# BMS028B_FETs.net
KiCad netlist of a schematic drawn in Altium Designer
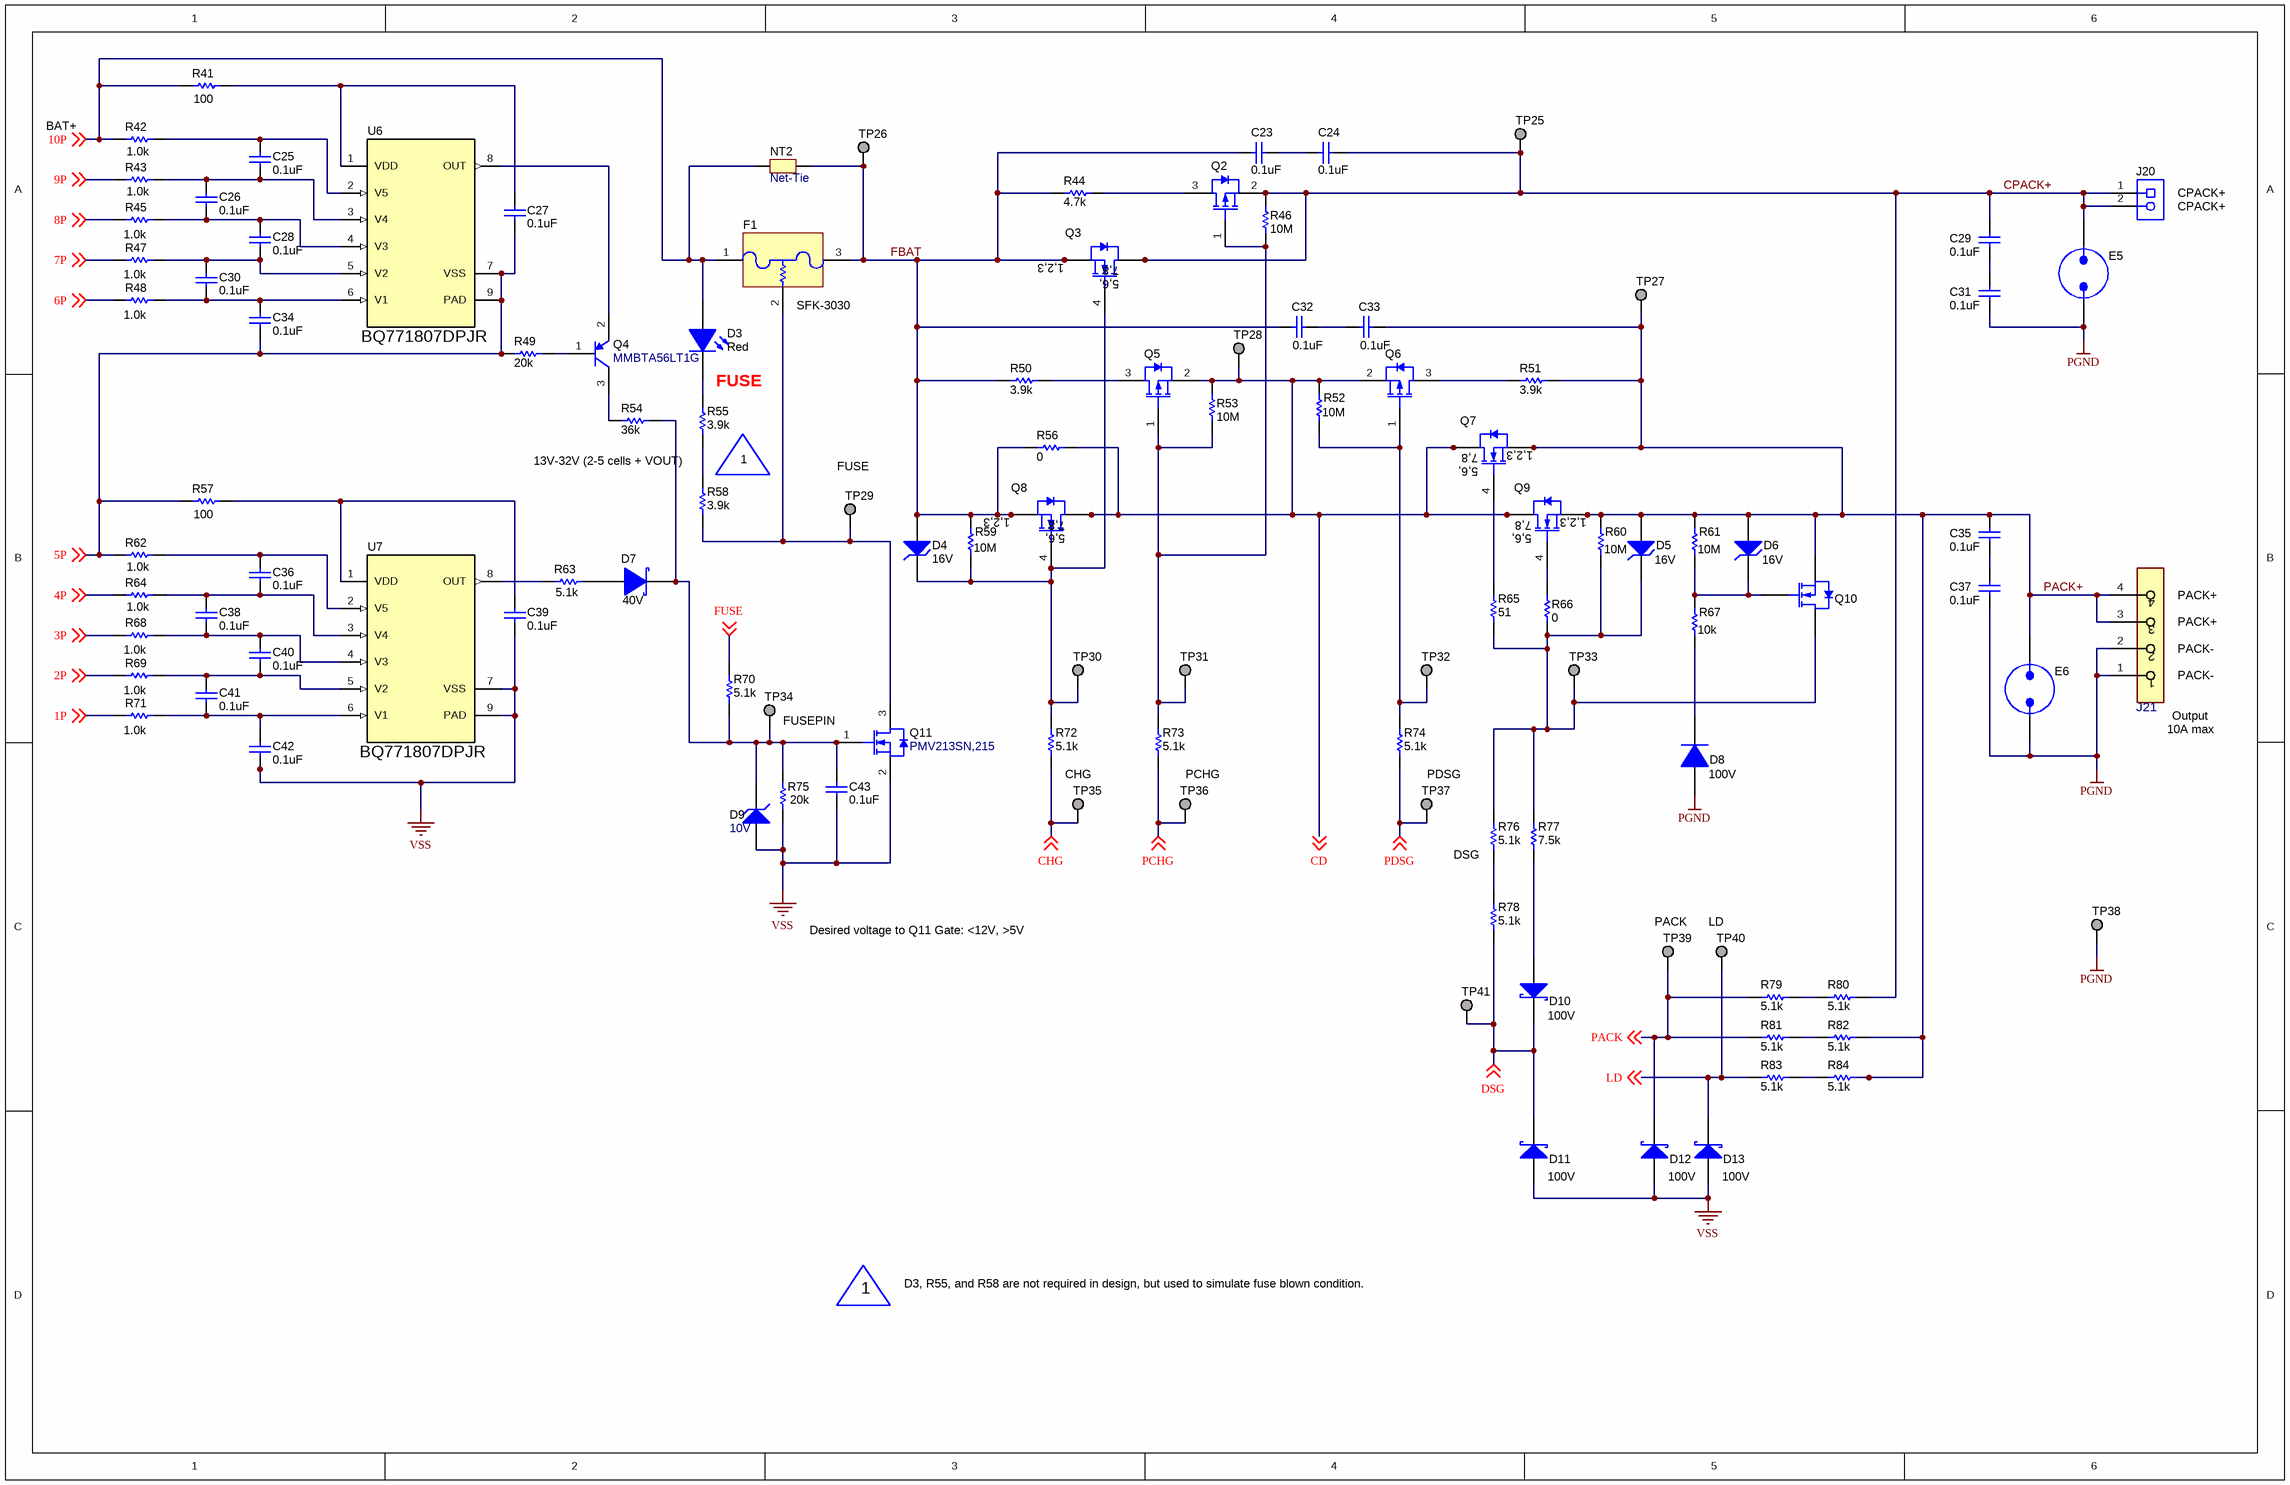
[diagram p0: BMS028B_FETs.SchDoc]

(export (version "E")
  (design (tool "Eeschema 10.0.6"))
  (components
    (comp (ref "C23")
      (value "GCJ188R72A104KA01D")
      (footprint "0603")
      (description "CAP, CERM, 0.1 uF, 100 V,+/- 10%, X7R, AEC-Q200 Grade 1, 0603")
      (fields
        (field (name "MANUFACTURER") "MuRata")
        (field (name "CAP_F") "0.1uF")
        (field (name "PUBLISHER") "Texas Instruments")
      )
      (libsource (lib "Altium Vault - TI") (part "Capacitor"))
    )
    (comp (ref "C24")
      (value "GCJ188R72A104KA01D")
      (footprint "0603")
      (description "CAP, CERM, 0.1 uF, 100 V,+/- 10%, X7R, AEC-Q200 Grade 1, 0603")
      (fields
        (field (name "MANUFACTURER") "MuRata")
        (field (name "CAP_F") "0.1uF")
        (field (name "PUBLISHER") "Texas Instruments")
      )
      (libsource (lib "Altium Vault - TI") (part "Capacitor"))
    )
    (comp (ref "C25")
      (value "885012206095")
      (footprint "0603")
      (description "CAP, CERM, 0.1 uF, 50 V, +/- 10%, X7R, 0603")
      (fields
        (field (name "VALUEDISPLAYED") "0.1uF")
        (field (name "MANUFACTURER") "Wurth Elektronik")
        (field (name "PUBLISHER") "Texas Instruments")
      )
      (libsource (lib "Altium Vault - TI") (part "Capacitor"))
    )
    (comp (ref "C26")
      (value "885012206095")
      (footprint "0603")
      (description "CAP, CERM, 0.1 uF, 50 V, +/- 10%, X7R, 0603")
      (fields
        (field (name "VALUEDISPLAYED") "0.1uF")
        (field (name "MANUFACTURER") "Wurth Elektronik")
        (field (name "PUBLISHER") "Texas Instruments")
      )
      (libsource (lib "Altium Vault - TI") (part "Capacitor"))
    )
    (comp (ref "C27")
      (value "885012206095")
      (footprint "0603")
      (description "CAP, CERM, 0.1 uF, 50 V, +/- 10%, X7R, 0603")
      (fields
        (field (name "VALUEDISPLAYED") "0.1uF")
        (field (name "MANUFACTURER") "Wurth Elektronik")
        (field (name "PUBLISHER") "Texas Instruments")
      )
      (libsource (lib "Altium Vault - TI") (part "Capacitor"))
    )
    (comp (ref "C28")
      (value "885012206095")
      (footprint "0603")
      (description "CAP, CERM, 0.1 uF, 50 V, +/- 10%, X7R, 0603")
      (fields
        (field (name "VALUEDISPLAYED") "0.1uF")
        (field (name "MANUFACTURER") "Wurth Elektronik")
        (field (name "PUBLISHER") "Texas Instruments")
      )
      (libsource (lib "Altium Vault - TI") (part "Capacitor"))
    )
    (comp (ref "C29")
      (value "GCJ188R72A104KA01D")
      (footprint "0603")
      (description "CAP, CERM, 0.1 uF, 100 V,+/- 10%, X7R, AEC-Q200 Grade 1, 0603")
      (fields
        (field (name "MANUFACTURER") "MuRata")
        (field (name "CAP_F") "0.1uF")
        (field (name "PUBLISHER") "Texas Instruments")
      )
      (libsource (lib "Altium Vault - TI") (part "Capacitor"))
    )
    (comp (ref "C30")
      (value "885012206095")
      (footprint "0603")
      (description "CAP, CERM, 0.1 uF, 50 V, +/- 10%, X7R, 0603")
      (fields
        (field (name "VALUEDISPLAYED") "0.1uF")
        (field (name "MANUFACTURER") "Wurth Elektronik")
        (field (name "PUBLISHER") "Texas Instruments")
      )
      (libsource (lib "Altium Vault - TI") (part "Capacitor"))
    )
    (comp (ref "C31")
      (value "GCJ188R72A104KA01D")
      (footprint "0603")
      (description "CAP, CERM, 0.1 uF, 100 V,+/- 10%, X7R, AEC-Q200 Grade 1, 0603")
      (fields
        (field (name "MANUFACTURER") "MuRata")
        (field (name "CAP_F") "0.1uF")
        (field (name "PUBLISHER") "Texas Instruments")
      )
      (libsource (lib "Altium Vault - TI") (part "Capacitor"))
    )
    (comp (ref "C32")
      (value "GCJ188R72A104KA01D")
      (footprint "0603")
      (description "CAP, CERM, 0.1 uF, 100 V,+/- 10%, X7R, AEC-Q200 Grade 1, 0603")
      (fields
        (field (name "MANUFACTURER") "MuRata")
        (field (name "VALUEDISPLAYED") "0.1uF")
        (field (name "PUBLISHER") "Texas Instruments")
      )
      (libsource (lib "Altium Vault - TI") (part "Capacitor"))
    )
    (comp (ref "C33")
      (value "GCJ188R72A104KA01D")
      (footprint "0603")
      (description "CAP, CERM, 0.1 uF, 100 V,+/- 10%, X7R, AEC-Q200 Grade 1, 0603")
      (fields
        (field (name "MANUFACTURER") "MuRata")
        (field (name "VALUEDISPLAYED") "0.1uF")
        (field (name "PUBLISHER") "Texas Instruments")
      )
      (libsource (lib "Altium Vault - TI") (part "Capacitor"))
    )
    (comp (ref "C34")
      (value "885012206095")
      (footprint "0603")
      (description "CAP, CERM, 0.1 uF, 50 V, +/- 10%, X7R, 0603")
      (fields
        (field (name "VALUEDISPLAYED") "0.1uF")
        (field (name "MANUFACTURER") "Wurth Elektronik")
        (field (name "PUBLISHER") "Texas Instruments")
      )
      (libsource (lib "Altium Vault - TI") (part "Capacitor"))
    )
    (comp (ref "C35")
      (value "GCJ188R72A104KA01D")
      (footprint "0603")
      (description "CAP, CERM, 0.1 uF, 100 V,+/- 10%, X7R, AEC-Q200 Grade 1, 0603")
      (fields
        (field (name "MANUFACTURER") "MuRata")
        (field (name "CAP_F") "0.1uF")
        (field (name "PUBLISHER") "Texas Instruments")
      )
      (libsource (lib "Altium Vault - TI") (part "Capacitor"))
    )
    (comp (ref "C36")
      (value "885012206095")
      (footprint "0603")
      (description "CAP, CERM, 0.1 uF, 50 V, +/- 10%, X7R, 0603")
      (fields
        (field (name "VALUEDISPLAYED") "0.1uF")
        (field (name "MANUFACTURER") "Wurth Elektronik")
        (field (name "PUBLISHER") "Texas Instruments")
      )
      (libsource (lib "Altium Vault - TI") (part "Capacitor"))
    )
    (comp (ref "C37")
      (value "GCJ188R72A104KA01D")
      (footprint "0603")
      (description "CAP, CERM, 0.1 uF, 100 V,+/- 10%, X7R, AEC-Q200 Grade 1, 0603")
      (fields
        (field (name "MANUFACTURER") "MuRata")
        (field (name "CAP_F") "0.1uF")
        (field (name "PUBLISHER") "Texas Instruments")
      )
      (libsource (lib "Altium Vault - TI") (part "Capacitor"))
    )
    (comp (ref "C38")
      (value "885012206095")
      (footprint "0603")
      (description "CAP, CERM, 0.1 uF, 50 V, +/- 10%, X7R, 0603")
      (fields
        (field (name "VALUEDISPLAYED") "0.1uF")
        (field (name "MANUFACTURER") "Wurth Elektronik")
        (field (name "PUBLISHER") "Texas Instruments")
      )
      (libsource (lib "Altium Vault - TI") (part "Capacitor"))
    )
    (comp (ref "C39")
      (value "885012206095")
      (footprint "0603")
      (description "CAP, CERM, 0.1 uF, 50 V, +/- 10%, X7R, 0603")
      (fields
        (field (name "VALUEDISPLAYED") "0.1uF")
        (field (name "MANUFACTURER") "Wurth Elektronik")
        (field (name "PUBLISHER") "Texas Instruments")
      )
      (libsource (lib "Altium Vault - TI") (part "Capacitor"))
    )
    (comp (ref "C40")
      (value "885012206095")
      (footprint "0603")
      (description "CAP, CERM, 0.1 uF, 50 V, +/- 10%, X7R, 0603")
      (fields
        (field (name "VALUEDISPLAYED") "0.1uF")
        (field (name "MANUFACTURER") "Wurth Elektronik")
        (field (name "PUBLISHER") "Texas Instruments")
      )
      (libsource (lib "Altium Vault - TI") (part "Capacitor"))
    )
    (comp (ref "C41")
      (value "885012206095")
      (footprint "0603")
      (description "CAP, CERM, 0.1 uF, 50 V, +/- 10%, X7R, 0603")
      (fields
        (field (name "VALUEDISPLAYED") "0.1uF")
        (field (name "MANUFACTURER") "Wurth Elektronik")
        (field (name "PUBLISHER") "Texas Instruments")
      )
      (libsource (lib "Altium Vault - TI") (part "Capacitor"))
    )
    (comp (ref "C42")
      (value "885012206095")
      (footprint "0603")
      (description "CAP, CERM, 0.1 uF, 50 V, +/- 10%, X7R, 0603")
      (fields
        (field (name "VALUEDISPLAYED") "0.1uF")
        (field (name "MANUFACTURER") "Wurth Elektronik")
        (field (name "PUBLISHER") "Texas Instruments")
      )
      (libsource (lib "Altium Vault - TI") (part "Capacitor"))
    )
    (comp (ref "C43")
      (value "885012206095")
      (footprint "0603")
      (description "CAP, CERM, 0.1 uF, 50 V, +/- 10%, X7R, 0603")
      (fields
        (field (name "VALUEDISPLAYED") "0.1uF")
        (field (name "MANUFACTURER") "Wurth Elektronik")
        (field (name "PUBLISHER") "Texas Instruments")
      )
      (libsource (lib "Altium Vault - TI") (part "Capacitor"))
    )
    (comp (ref "D3")
      (value "Red")
      (footprint "WL-SMCW_RED")
      (description "LED, Red, SMD")
      (fields (field (name "MANUFACTURER") "Wurth Elektronik") (field (name "PARTNUMBER") "150060RS75000"))
      (libsource (lib "Altium Vault - TI") (part "CMP-0002947-3"))
    )
    (comp (ref "D4")
      (value "16V")
      (footprint "SOD-123")
      (description "Diode, Zener, 16 V, 500 mW, SOD-123")
      (fields (field (name "MANUFACTURER") "Diodes Inc.") (field (name "PARTNUMBER") "MMSZ5246B-7-F"))
      (libsource (lib "Altium Vault - TI") (part "Zener"))
    )
    (comp (ref "D5")
      (value "16V")
      (footprint "SOD-123")
      (description "Diode, Zener, 16 V, 500 mW, SOD-123")
      (fields (field (name "PARTNUMBER") "MMSZ5246B-7-F") (field (name "MANUFACTURER") "Diodes Inc."))
      (libsource (lib "Altium Vault - TI") (part "CMP-0005754-4"))
    )
    (comp (ref "D6")
      (value "16V")
      (footprint "SOD-123")
      (description "Diode, Zener, 16 V, 500 mW, SOD-123")
      (fields (field (name "PARTNUMBER") "MMSZ5246B-7-F") (field (name "MANUFACTURER") "Diodes Inc."))
      (libsource (lib "Altium Vault - TI") (part "CMP-0005754-4"))
    )
    (comp (ref "D7")
      (value "40V")
      (footprint "SOT-323")
      (description "Diode, Schottky, 40 V, 0.2 A, SOT-323")
      (fields (field (name "PARTNUMBER") "BAS40W-7-F") (field (name "MANUFACTURER") "Diodes Inc."))
      (libsource (lib "Altium Vault - TI") (part "CMP-0028438-2"))
    )
    (comp (ref "D8")
      (value "100V")
      (footprint "SOD-123")
      (description "Diode, Ultrafast, 100 V, 0.15 A, SOD-123")
      (fields (field (name "PARTNUMBER") "1N4148W-7-F") (field (name "MANUFACTURER") "Diodes Inc."))
      (libsource (lib "Altium Vault - TI") (part "CMP-0029001-2"))
    )
    (comp (ref "D9")
      (value "10V")
      (footprint "SOD-123")
      (description "Diode, Zener, 10 V, 500 mW, SOD-123")
      (fields (field (name "MANUFACTURER") "ON Semiconductor") (field (name "PARTNUMBER") "MMSZ4697T1G"))
      (libsource (lib "Altium Vault - TI") (part "Zener"))
    )
    (comp (ref "D10")
      (value "BAT46W-7-F")
      (footprint "SOD-123")
      (description "Diode, Schottky, 100 V, 0.15 A, SOD-123")
      (fields (field (name "MANUFACTURER") "Diodes Inc.") (field (name "VR_V") "100V"))
      (libsource (lib "Altium Vault - TI") (part "DIODE_SCHOTTKY"))
    )
    (comp (ref "D11")
      (value "BAT46W-7-F")
      (footprint "SOD-123")
      (description "Diode, Schottky, 100 V, 0.15 A, SOD-123")
      (fields (field (name "MANUFACTURER") "Diodes Inc.") (field (name "VR_V") "100V"))
      (libsource (lib "Altium Vault - TI") (part "DIODE_SCHOTTKY"))
    )
    (comp (ref "D12")
      (value "BAT46W-7-F")
      (footprint "SOD-123")
      (description "Diode, Schottky, 100 V, 0.15 A, SOD-123")
      (fields (field (name "MANUFACTURER") "Diodes Inc.") (field (name "VR_V") "100V"))
      (libsource (lib "Altium Vault - TI") (part "DIODE_SCHOTTKY"))
    )
    (comp (ref "D13")
      (value "BAT46W-7-F")
      (footprint "SOD-123")
      (description "Diode, Schottky, 100 V, 0.15 A, SOD-123")
      (fields (field (name "MANUFACTURER") "Diodes Inc.") (field (name "VR_V") "100V"))
      (libsource (lib "Altium Vault - TI") (part "DIODE_SCHOTTKY"))
    )
    (comp (ref "E5")
      (value "Spark Gap")
      (footprint "SPARK_GAP2")
      (libsource (lib "Altium Vault - TI") (part "CMP-0079939-1"))
    )
    (comp (ref "E6")
      (value "Spark Gap")
      (footprint "SPARK_GAP2")
      (libsource (lib "Altium Vault - TI") (part "CMP-0079939-1"))
    )
    (comp (ref "F1")
      (value "SFK-3030")
      (footprint "FUSE_SFK-xx30x")
      (description "Fuse, 30 A, 62 VDC, SMD")
      (fields (field (name "MANUFACTURER") "Dexerials Corporation"))
      (libsource (lib "Altium Vault - TI") (part "FUSE_SFK-XX30X"))
    )
    (comp (ref "J20")
      (value "ED555/2DS")
      (footprint "TERM_BLK_ED555-2DS")
      (description "Terminal Block, 3.5mm Pitch, 2x1, TH")
      (fields
        (field (name "MANUFACTURER") "On-Shore Technology")
        (field (name "PUBLISHER") "Texas Instruments")
      )
      (libsource (lib "Altium Vault - TI") (part "CMP-0074913-1"))
    )
    (comp (ref "J21")
      (value "OSTTE040161")
      (footprint "FP-OSTTE040161_HDR4-MFG")
      (description "TERM BLOCK 3.5MM VERT 4POS PCB")
      (fields (field (name "MANUFACTURER") "On Shore Technology"))
      (libsource (lib "Altium Vault - TI") (part "SYM-OSTTE040161"))
    )
    (comp (ref "NT2")
      (value "Net-Tie")
      (footprint "Net-Tie_50milWide_30milLong")
      (description "Single point connection between nets.")
      (libsource (lib "Altium Vault - TI") (part "Net-Tie"))
    )
    (comp (ref "Q2")
      (value "ZXMP10A13FTA")
      (footprint "SOT-23")
      (description "MOSFET, P-CH, -100 V, -0.6 A, SOT-23")
      (fields (field (name "MANUFACTURER") "Diodes Inc."))
      (libsource (lib "Altium Vault - TI") (part "MOSFET_P_D3G1S2"))
    )
    (comp (ref "Q3")
      (value "CSD19534Q5A")
      (footprint "DQJ0008A")
      (description "MOSFET, N-CH, 100 V, 10 A, DQJ0008A (VSONP-8)")
      (fields
        (field (name "MANUFACTURER") "Texas Instruments")
        (field (name "PUBLISHER") "Texas Instruments")
      )
      (libsource (lib "Altium Vault - TI") (part "MOSFET_N_D56789G4S123"))
    )
    (comp (ref "Q4")
      (value "MMBTA56LT1G")
      (footprint "SOT-23")
      (description "Transistor, PNP, 80 V, 0.5 A, SOT-23")
      (fields (field (name "MANUFACTURER") "ON Semiconductor") (field (name "PUBLISHER") "Texas Instruments"))
      (libsource (lib "Altium Vault - TI") (part "BJT_PNP_C3B1E2"))
    )
    (comp (ref "Q5")
      (value "ZXMP10A13FTA")
      (footprint "SOT-23")
      (description "MOSFET, P-CH, -100 V, -0.6 A, SOT-23")
      (fields (field (name "MANUFACTURER") "Diodes Inc."))
      (libsource (lib "Altium Vault - TI") (part "MOSFET_P_D3G1S2"))
    )
    (comp (ref "Q6")
      (value "ZXMP10A13FTA")
      (footprint "SOT-23")
      (description "MOSFET, P-CH, -100 V, -0.6 A, SOT-23")
      (fields (field (name "MANUFACTURER") "Diodes Inc."))
      (libsource (lib "Altium Vault - TI") (part "MOSFET_P_D3G1S2"))
    )
    (comp (ref "Q7")
      (value "CSD19532Q5B")
      (footprint "DNK0008A")
      (description "MOSFET, N-CH, 100 V, 17 A, DNK0008A (VSON-CLIP-8)")
      (fields (field (name "MANUFACTURER") "Texas Instruments"))
      (libsource (lib "Altium Vault - TI") (part "MOSFET_N_D56789G4S123"))
    )
    (comp (ref "Q8")
      (value "CSD19532Q5B")
      (footprint "DNK0008A")
      (description "MOSFET, N-CH, 100 V, 17 A, DNK0008A (VSON-CLIP-8)")
      (fields (field (name "MANUFACTURER") "Texas Instruments"))
      (libsource (lib "Altium Vault - TI") (part "MOSFET_N_D56789G4S123"))
    )
    (comp (ref "Q9")
      (value "CSD19532Q5B")
      (footprint "DNK0008A")
      (description "MOSFET, N-CH, 100 V, 17 A, DNK0008A (VSON-CLIP-8)")
      (fields (field (name "MANUFACTURER") "Texas Instruments"))
      (libsource (lib "Altium Vault - TI") (part "MOSFET_N_D56789G4S123"))
    )
    (comp (ref "Q10")
      (value "MOSFET_N_D3G1S2")
      (footprint "SOT-323")
      (description "MOSFET, N-CH, 60 V, 0.31 A, SOT-323")
      (fields
        (field (name "PARTNUMBER") "2N7002KW")
        (field (name "MANUFACTURER") "Fairchild Semiconductor")
        (field (name "PUBLISHER") "Texas Instruments")
      )
      (libsource (lib "Altium Vault - TI") (part "CMP-0000774-1"))
    )
    (comp (ref "Q11")
      (value "PMV213SN,215")
      (footprint "SOT-23")
      (description "MOSFET, N-CH, 100 V, 1.9 A, SOT-23")
      (fields (field (name "MANUFACTURER") "Nexperia"))
      (libsource (lib "Altium Vault - TI") (part "MOSFET_N_D3G1S2"))
    )
    (comp (ref "R41")
      (value "Resistor")
      (footprint "0603")
      (description "RES, 100, 5%, 0.1 W, AEC-Q200 Grade 0, 0603")
      (fields
        (field (name "PARTNUMBER") "CRCW0603100RJNEA")
        (field (name "MANUFACTURER") "Vishay-Dale")
        (field (name "VALUEDISPLAYED") "100")
        (field (name "PUBLISHER") "Texas Instruments")
      )
      (libsource (lib "Altium Vault - TI") (part "Resistor"))
    )
    (comp (ref "R42")
      (value "Resistor")
      (footprint "0603")
      (description "RES, 1.0 k, 5%, 0.1 W, AEC-Q200 Grade 0, 0603")
      (fields
        (field (name "PARTNUMBER") "CRCW06031K00JNEA")
        (field (name "MANUFACTURER") "Vishay-Dale")
        (field (name "VALUEDISPLAYED") "1.0k")
        (field (name "PUBLISHER") "Texas Instruments")
      )
      (libsource (lib "Altium Vault - TI") (part "Resistor"))
    )
    (comp (ref "R43")
      (value "Resistor")
      (footprint "0603")
      (description "RES, 1.0 k, 5%, 0.1 W, AEC-Q200 Grade 0, 0603")
      (fields
        (field (name "PARTNUMBER") "CRCW06031K00JNEA")
        (field (name "MANUFACTURER") "Vishay-Dale")
        (field (name "VALUEDISPLAYED") "1.0k")
        (field (name "PUBLISHER") "Texas Instruments")
      )
      (libsource (lib "Altium Vault - TI") (part "Resistor"))
    )
    (comp (ref "R44")
      (value "CRCW25124K70JNEG")
      (footprint "2512")
      (description "RES, 4.7 k, 5%, 1 W, AEC-Q200 Grade 0, 2512")
      (fields (field (name "MANUFACTURER") "Vishay-Dale") (field (name "VALUEDISPLAYED") "4.7k"))
      (libsource (lib "Altium Vault - TI") (part "Resistor"))
    )
    (comp (ref "R45")
      (value "Resistor")
      (footprint "0603")
      (description "RES, 1.0 k, 5%, 0.1 W, AEC-Q200 Grade 0, 0603")
      (fields
        (field (name "PARTNUMBER") "CRCW06031K00JNEA")
        (field (name "MANUFACTURER") "Vishay-Dale")
        (field (name "VALUEDISPLAYED") "1.0k")
        (field (name "PUBLISHER") "Texas Instruments")
      )
      (libsource (lib "Altium Vault - TI") (part "Resistor"))
    )
    (comp (ref "R46")
      (value "Resistor")
      (footprint "0603")
      (description "RES, 10 M, 5%, 0.1 W, AEC-Q200 Grade 0, 0603")
      (fields
        (field (name "PARTNUMBER") "CRCW060310M0JNEA")
        (field (name "MANUFACTURER") "Vishay-Dale")
        (field (name "VALUEDISPLAYED") "10M")
        (field (name "PUBLISHER") "Texas Instruments")
      )
      (libsource (lib "Altium Vault - TI") (part "Resistor"))
    )
    (comp (ref "R47")
      (value "Resistor")
      (footprint "0603")
      (description "RES, 1.0 k, 5%, 0.1 W, AEC-Q200 Grade 0, 0603")
      (fields
        (field (name "PARTNUMBER") "CRCW06031K00JNEA")
        (field (name "MANUFACTURER") "Vishay-Dale")
        (field (name "VALUEDISPLAYED") "1.0k")
        (field (name "PUBLISHER") "Texas Instruments")
      )
      (libsource (lib "Altium Vault - TI") (part "Resistor"))
    )
    (comp (ref "R48")
      (value "Resistor")
      (footprint "0603")
      (description "RES, 1.0 k, 5%, 0.1 W, AEC-Q200 Grade 0, 0603")
      (fields
        (field (name "PARTNUMBER") "CRCW06031K00JNEA")
        (field (name "MANUFACTURER") "Vishay-Dale")
        (field (name "VALUEDISPLAYED") "1.0k")
        (field (name "PUBLISHER") "Texas Instruments")
      )
      (libsource (lib "Altium Vault - TI") (part "Resistor"))
    )
    (comp (ref "R49")
      (value "CRCW060320K0JNEA")
      (footprint "0603")
      (description "RES, 20 k, 5%, 0.1 W, AEC-Q200 Grade 0, 0603")
      (fields (field (name "MANUFACTURER") "Vishay-Dale") (field (name "VALUEDISPLAYED") "20k"))
      (libsource (lib "Altium Vault - TI") (part "Resistor"))
    )
    (comp (ref "R50")
      (value "CRCW25123K90JNEG")
      (footprint "2512")
      (description "RES, 3.9 k, 5%, 1 W, AEC-Q200 Grade 0, 2512")
      (fields (field (name "MANUFACTURER") "Vishay-Dale") (field (name "VALUEDISPLAYED") "3.9k"))
      (libsource (lib "Altium Vault - TI") (part "Resistor"))
    )
    (comp (ref "R51")
      (value "CRCW25123K90JNEG")
      (footprint "2512")
      (description "RES, 3.9 k, 5%, 1 W, AEC-Q200 Grade 0, 2512")
      (fields (field (name "MANUFACTURER") "Vishay-Dale") (field (name "VALUEDISPLAYED") "3.9k"))
      (libsource (lib "Altium Vault - TI") (part "Resistor"))
    )
    (comp (ref "R52")
      (value "Resistor")
      (footprint "0603")
      (description "RES, 10 M, 5%, 0.1 W, AEC-Q200 Grade 0, 0603")
      (fields
        (field (name "PARTNUMBER") "CRCW060310M0JNEA")
        (field (name "MANUFACTURER") "Vishay-Dale")
        (field (name "VALUEDISPLAYED") "10M")
        (field (name "PUBLISHER") "Texas Instruments")
      )
      (libsource (lib "Altium Vault - TI") (part "Resistor"))
    )
    (comp (ref "R53")
      (value "Resistor")
      (footprint "0603")
      (description "RES, 10 M, 5%, 0.1 W, AEC-Q200 Grade 0, 0603")
      (fields
        (field (name "PARTNUMBER") "CRCW060310M0JNEA")
        (field (name "MANUFACTURER") "Vishay-Dale")
        (field (name "VALUEDISPLAYED") "10M")
        (field (name "PUBLISHER") "Texas Instruments")
      )
      (libsource (lib "Altium Vault - TI") (part "Resistor"))
    )
    (comp (ref "R54")
      (value "CRCW060336K0JNEA")
      (footprint "0603")
      (description "RES, 36 k, 5%, 0.1 W, AEC-Q200 Grade 0, 0603")
      (fields (field (name "MANUFACTURER") "Vishay-Dale") (field (name "VALUEDISPLAYED") "36k"))
      (libsource (lib "Altium Vault - TI") (part "Resistor"))
    )
    (comp (ref "R55")
      (value "CRCW12063K90JNEA")
      (footprint "1206")
      (description "RES, 3.9 k, 5%, 0.25 W, AEC-Q200 Grade 0, 1206")
      (fields (field (name "MANUFACTURER") "Vishay-Dale") (field (name "VALUEDISPLAYED") "3.9k"))
      (libsource (lib "Altium Vault - TI") (part "Resistor"))
    )
    (comp (ref "R56")
      (value "Resistor")
      (footprint "2512_WIDE_VISHAY")
      (description "RES, 0, 5%, 2 W, 2512 WIDE")
      (fields
        (field (name "PARTNUMBER") "RCL12250000Z0EG")
        (field (name "VALUEDISPLAYED") "0")
        (field (name "MANUFACTURER") "Vishay Draloric")
        (field (name "PUBLISHER") "Texas Instruments")
      )
      (libsource (lib "Altium Vault - TI") (part "Resistor"))
    )
    (comp (ref "R57")
      (value "Resistor")
      (footprint "0603")
      (description "RES, 100, 5%, 0.1 W, AEC-Q200 Grade 0, 0603")
      (fields
        (field (name "PARTNUMBER") "CRCW0603100RJNEA")
        (field (name "MANUFACTURER") "Vishay-Dale")
        (field (name "VALUEDISPLAYED") "100")
        (field (name "PUBLISHER") "Texas Instruments")
      )
      (libsource (lib "Altium Vault - TI") (part "Resistor"))
    )
    (comp (ref "R58")
      (value "CRCW12063K90JNEA")
      (footprint "1206")
      (description "RES, 3.9 k, 5%, 0.25 W, AEC-Q200 Grade 0, 1206")
      (fields (field (name "MANUFACTURER") "Vishay-Dale") (field (name "VALUEDISPLAYED") "3.9k"))
      (libsource (lib "Altium Vault - TI") (part "Resistor"))
    )
    (comp (ref "R59")
      (value "Resistor")
      (footprint "0603")
      (description "RES, 10 M, 5%, 0.1 W, AEC-Q200 Grade 0, 0603")
      (fields
        (field (name "PARTNUMBER") "CRCW060310M0JNEA")
        (field (name "MANUFACTURER") "Vishay-Dale")
        (field (name "VALUEDISPLAYED") "10M")
        (field (name "PUBLISHER") "Texas Instruments")
      )
      (libsource (lib "Altium Vault - TI") (part "Resistor"))
    )
    (comp (ref "R60")
      (value "Resistor")
      (footprint "0603")
      (description "RES, 10 M, 5%, 0.1 W, AEC-Q200 Grade 0, 0603")
      (fields
        (field (name "PARTNUMBER") "CRCW060310M0JNEA")
        (field (name "MANUFACTURER") "Vishay-Dale")
        (field (name "VALUEDISPLAYED") "10M")
        (field (name "PUBLISHER") "Texas Instruments")
      )
      (libsource (lib "Altium Vault - TI") (part "Resistor"))
    )
    (comp (ref "R61")
      (value "Resistor")
      (footprint "0603")
      (description "RES, 10 M, 5%, 0.1 W, AEC-Q200 Grade 0, 0603")
      (fields
        (field (name "PARTNUMBER") "CRCW060310M0JNEA")
        (field (name "MANUFACTURER") "Vishay-Dale")
        (field (name "VALUEDISPLAYED") "10M")
        (field (name "PUBLISHER") "Texas Instruments")
      )
      (libsource (lib "Altium Vault - TI") (part "Resistor"))
    )
    (comp (ref "R62")
      (value "Resistor")
      (footprint "0603")
      (description "RES, 1.0 k, 5%, 0.1 W, AEC-Q200 Grade 0, 0603")
      (fields
        (field (name "PARTNUMBER") "CRCW06031K00JNEA")
        (field (name "MANUFACTURER") "Vishay-Dale")
        (field (name "VALUEDISPLAYED") "1.0k")
        (field (name "PUBLISHER") "Texas Instruments")
      )
      (libsource (lib "Altium Vault - TI") (part "Resistor"))
    )
    (comp (ref "R63")
      (value "Resistor")
      (footprint "0603")
      (description "RES, 5.1 k, 5%, 0.1 W, AEC-Q200 Grade 0, 0603")
      (fields
        (field (name "PARTNUMBER") "CRCW06035K10JNEA")
        (field (name "MANUFACTURER") "Vishay-Dale")
        (field (name "VALUEDISPLAYED") "5.1k")
        (field (name "PUBLISHER") "Texas Instruments")
      )
      (libsource (lib "Altium Vault - TI") (part "Resistor"))
    )
    (comp (ref "R64")
      (value "Resistor")
      (footprint "0603")
      (description "RES, 1.0 k, 5%, 0.1 W, AEC-Q200 Grade 0, 0603")
      (fields
        (field (name "PARTNUMBER") "CRCW06031K00JNEA")
        (field (name "MANUFACTURER") "Vishay-Dale")
        (field (name "VALUEDISPLAYED") "1.0k")
        (field (name "PUBLISHER") "Texas Instruments")
      )
      (libsource (lib "Altium Vault - TI") (part "Resistor"))
    )
    (comp (ref "R65")
      (value "CRCW060351R0JNEA")
      (footprint "0603")
      (description "RES, 51, 5%, 0.1 W, AEC-Q200 Grade 0, 0603")
      (fields (field (name "MANUFACTURER") "Vishay-Dale") (field (name "VALUEDISPLAYED") "51"))
      (libsource (lib "Altium Vault - TI") (part "Resistor"))
    )
    (comp (ref "R66")
      (value "CRCW06030000Z0EA")
      (footprint "0603")
      (description "RES, 0, 5%, 0.1 W, AEC-Q200 Grade 0, 0603")
      (fields (field (name "MANUFACTURER") "Vishay-Dale") (field (name "VALUEDISPLAYED") "0"))
      (libsource (lib "Altium Vault - TI") (part "Resistor"))
    )
    (comp (ref "R67")
      (value "Resistor")
      (footprint "0603")
      (description "RES, 10 k, 5%, 0.1 W, AEC-Q200 Grade 0, 0603")
      (fields
        (field (name "PARTNUMBER") "CRCW060310K0JNEA")
        (field (name "MANUFACTURER") "Vishay-Dale")
        (field (name "VALUEDISPLAYED") "10k")
        (field (name "PUBLISHER") "Texas Instruments")
      )
      (libsource (lib "Altium Vault - TI") (part "Resistor"))
    )
    (comp (ref "R68")
      (value "Resistor")
      (footprint "0603")
      (description "RES, 1.0 k, 5%, 0.1 W, AEC-Q200 Grade 0, 0603")
      (fields
        (field (name "PARTNUMBER") "CRCW06031K00JNEA")
        (field (name "MANUFACTURER") "Vishay-Dale")
        (field (name "VALUEDISPLAYED") "1.0k")
        (field (name "PUBLISHER") "Texas Instruments")
      )
      (libsource (lib "Altium Vault - TI") (part "Resistor"))
    )
    (comp (ref "R69")
      (value "Resistor")
      (footprint "0603")
      (description "RES, 1.0 k, 5%, 0.1 W, AEC-Q200 Grade 0, 0603")
      (fields
        (field (name "PARTNUMBER") "CRCW06031K00JNEA")
        (field (name "MANUFACTURER") "Vishay-Dale")
        (field (name "VALUEDISPLAYED") "1.0k")
        (field (name "PUBLISHER") "Texas Instruments")
      )
      (libsource (lib "Altium Vault - TI") (part "Resistor"))
    )
    (comp (ref "R70")
      (value "Resistor")
      (footprint "0603")
      (description "RES, 5.1 k, 5%, 0.1 W, AEC-Q200 Grade 0, 0603")
      (fields
        (field (name "PARTNUMBER") "CRCW06035K10JNEA")
        (field (name "MANUFACTURER") "Vishay-Dale")
        (field (name "VALUEDISPLAYED") "5.1k")
        (field (name "PUBLISHER") "Texas Instruments")
      )
      (libsource (lib "Altium Vault - TI") (part "Resistor"))
    )
    (comp (ref "R71")
      (value "Resistor")
      (footprint "0603")
      (description "RES, 1.0 k, 5%, 0.1 W, AEC-Q200 Grade 0, 0603")
      (fields
        (field (name "PARTNUMBER") "CRCW06031K00JNEA")
        (field (name "MANUFACTURER") "Vishay-Dale")
        (field (name "VALUEDISPLAYED") "1.0k")
        (field (name "PUBLISHER") "Texas Instruments")
      )
      (libsource (lib "Altium Vault - TI") (part "Resistor"))
    )
    (comp (ref "R72")
      (value "CRCW06035K10JNEA")
      (footprint "0603")
      (description "RES, 5.1 k, 5%, 0.1 W, AEC-Q200 Grade 0, 0603")
      (fields (field (name "VALUEDISPLAYED") "5.1k") (field (name "MANUFACTURER") "Vishay-Dale"))
      (libsource (lib "Altium Vault - TI") (part "Resistor"))
    )
    (comp (ref "R73")
      (value "CRCW06035K10JNEA")
      (footprint "0603")
      (description "RES, 5.1 k, 5%, 0.1 W, AEC-Q200 Grade 0, 0603")
      (fields (field (name "VALUEDISPLAYED") "5.1k") (field (name "MANUFACTURER") "Vishay-Dale"))
      (libsource (lib "Altium Vault - TI") (part "Resistor"))
    )
    (comp (ref "R74")
      (value "CRCW06035K10JNEA")
      (footprint "0603")
      (description "RES, 5.1 k, 5%, 0.1 W, AEC-Q200 Grade 0, 0603")
      (fields (field (name "MANUFACTURER") "Vishay-Dale") (field (name "VALUEDISPLAYED") "5.1k"))
      (libsource (lib "Altium Vault - TI") (part "Resistor"))
    )
    (comp (ref "R75")
      (value "Resistor")
      (footprint "0603")
      (description "RES, 20 k, 5%, 0.1 W, AEC-Q200 Grade 0, 0603")
      (fields
        (field (name "PARTNUMBER") "CRCW060320K0JNEA")
        (field (name "MANUFACTURER") "Vishay-Dale")
        (field (name "VALUEDISPLAYED") "20k")
        (field (name "PUBLISHER") "Texas Instruments")
      )
      (libsource (lib "Altium Vault - TI") (part "Resistor"))
    )
    (comp (ref "R76")
      (value "CRCW12065K10JNEA")
      (footprint "1206")
      (description "RES, 5.1 k, 5%, 0.25 W, AEC-Q200 Grade 0, 1206")
      (fields (field (name "VALUEDISPLAYED") "5.1k") (field (name "MANUFACTURER") "Vishay-Dale"))
      (libsource (lib "Altium Vault - TI") (part "Resistor"))
    )
    (comp (ref "R77")
      (value "CRCW06037K50JNEA")
      (footprint "0603")
      (description "RES, 7.5 k, 5%, 0.1 W, AEC-Q200 Grade 0, 0603")
      (fields (field (name "MANUFACTURER") "Vishay-Dale") (field (name "VALUEDISPLAYED") "7.5k"))
      (libsource (lib "Altium Vault - TI") (part "Resistor"))
    )
    (comp (ref "R78")
      (value "CRCW12065K10JNEA")
      (footprint "1206")
      (description "RES, 5.1 k, 5%, 0.25 W, AEC-Q200 Grade 0, 1206")
      (fields (field (name "VALUEDISPLAYED") "5.1k") (field (name "MANUFACTURER") "Vishay-Dale"))
      (libsource (lib "Altium Vault - TI") (part "Resistor"))
    )
    (comp (ref "R79")
      (value "CRCW12065K10JNEA")
      (footprint "1206")
      (description "RES, 5.1 k, 5%, 0.25 W, AEC-Q200 Grade 0, 1206")
      (fields (field (name "VALUEDISPLAYED") "5.1k") (field (name "MANUFACTURER") "Vishay-Dale"))
      (libsource (lib "Altium Vault - TI") (part "Resistor"))
    )
    (comp (ref "R80")
      (value "CRCW12065K10JNEA")
      (footprint "1206")
      (description "RES, 5.1 k, 5%, 0.25 W, AEC-Q200 Grade 0, 1206")
      (fields (field (name "VALUEDISPLAYED") "5.1k") (field (name "MANUFACTURER") "Vishay-Dale"))
      (libsource (lib "Altium Vault - TI") (part "Resistor"))
    )
    (comp (ref "R81")
      (value "CRCW12065K10JNEA")
      (footprint "1206")
      (description "RES, 5.1 k, 5%, 0.25 W, AEC-Q200 Grade 0, 1206")
      (fields (field (name "VALUEDISPLAYED") "5.1k") (field (name "MANUFACTURER") "Vishay-Dale"))
      (libsource (lib "Altium Vault - TI") (part "Resistor"))
    )
    (comp (ref "R82")
      (value "CRCW12065K10JNEA")
      (footprint "1206")
      (description "RES, 5.1 k, 5%, 0.25 W, AEC-Q200 Grade 0, 1206")
      (fields (field (name "VALUEDISPLAYED") "5.1k") (field (name "MANUFACTURER") "Vishay-Dale"))
      (libsource (lib "Altium Vault - TI") (part "Resistor"))
    )
    (comp (ref "R83")
      (value "CRCW12065K10JNEA")
      (footprint "1206")
      (description "RES, 5.1 k, 5%, 0.25 W, AEC-Q200 Grade 0, 1206")
      (fields (field (name "VALUEDISPLAYED") "5.1k") (field (name "MANUFACTURER") "Vishay-Dale"))
      (libsource (lib "Altium Vault - TI") (part "Resistor"))
    )
    (comp (ref "R84")
      (value "CRCW12065K10JNEA")
      (footprint "1206")
      (description "RES, 5.1 k, 5%, 0.25 W, AEC-Q200 Grade 0, 1206")
      (fields (field (name "VALUEDISPLAYED") "5.1k") (field (name "MANUFACTURER") "Vishay-Dale"))
      (libsource (lib "Altium Vault - TI") (part "Resistor"))
    )
    (comp (ref "TP25")
      (value "TESTPOINT")
      (footprint "TP_VIA_060RND040")
      (description "TEST POINT.  No entry in BOM.")
      (libsource (lib "Altium Vault - TI") (part "CMP-0078143-2"))
    )
    (comp (ref "TP26")
      (value "TESTPOINT")
      (footprint "TP_VIA_060RND040")
      (description "TEST POINT.  No entry in BOM.")
      (libsource (lib "Altium Vault - TI") (part "CMP-0078143-2"))
    )
    (comp (ref "TP27")
      (value "TESTPOINT")
      (footprint "TP_VIA_060RND040")
      (description "TEST POINT.  No entry in BOM.")
      (libsource (lib "Altium Vault - TI") (part "CMP-0078143-2"))
    )
    (comp (ref "TP28")
      (value "TESTPOINT")
      (footprint "TP_VIA_060RND040")
      (description "TEST POINT.  No entry in BOM.")
      (libsource (lib "Altium Vault - TI") (part "CMP-0078143-2"))
    )
    (comp (ref "TP29")
      (value "TESTPOINT")
      (footprint "TP_VIA_060RND040")
      (description "TEST POINT.  No entry in BOM.")
      (libsource (lib "Altium Vault - TI") (part "CMP-0078143-2"))
    )
    (comp (ref "TP30")
      (value "TESTPOINT")
      (footprint "TP_VIA_060RND040")
      (description "TEST POINT.  No entry in BOM.")
      (libsource (lib "Altium Vault - TI") (part "CMP-0078143-2"))
    )
    (comp (ref "TP31")
      (value "TESTPOINT")
      (footprint "TP_VIA_060RND040")
      (description "TEST POINT.  No entry in BOM.")
      (libsource (lib "Altium Vault - TI") (part "CMP-0078143-2"))
    )
    (comp (ref "TP32")
      (value "TESTPOINT")
      (footprint "TP_VIA_060RND040")
      (description "TEST POINT.  No entry in BOM.")
      (libsource (lib "Altium Vault - TI") (part "CMP-0078143-2"))
    )
    (comp (ref "TP33")
      (value "TESTPOINT")
      (footprint "TP_VIA_060RND040")
      (description "TEST POINT.  No entry in BOM.")
      (libsource (lib "Altium Vault - TI") (part "CMP-0078143-2"))
    )
    (comp (ref "TP34")
      (value "TESTPOINT")
      (footprint "TP_VIA_060RND040")
      (description "TEST POINT.  No entry in BOM.")
      (libsource (lib "Altium Vault - TI") (part "CMP-0078143-2"))
    )
    (comp (ref "TP35")
      (value "TESTPOINT")
      (footprint "TP_VIA_060RND040")
      (description "TEST POINT.  No entry in BOM.")
      (libsource (lib "Altium Vault - TI") (part "CMP-0078143-2"))
    )
    (comp (ref "TP36")
      (value "TESTPOINT")
      (footprint "TP_VIA_060RND040")
      (description "TEST POINT.  No entry in BOM.")
      (libsource (lib "Altium Vault - TI") (part "CMP-0078143-2"))
    )
    (comp (ref "TP37")
      (value "TESTPOINT")
      (footprint "TP_VIA_060RND040")
      (description "TEST POINT.  No entry in BOM.")
      (libsource (lib "Altium Vault - TI") (part "CMP-0078143-2"))
    )
    (comp (ref "TP38")
      (value "TESTPOINT")
      (footprint "TP_VIA_060RND040")
      (description "TEST POINT.  No entry in BOM.")
      (libsource (lib "Altium Vault - TI") (part "CMP-0078143-2"))
    )
    (comp (ref "TP39")
      (value "TESTPOINT")
      (footprint "TP_VIA_060RND040")
      (description "TEST POINT.  No entry in BOM.")
      (libsource (lib "Altium Vault - TI") (part "CMP-0078143-2"))
    )
    (comp (ref "TP40")
      (value "TESTPOINT")
      (footprint "TP_VIA_060RND040")
      (description "TEST POINT.  No entry in BOM.")
      (libsource (lib "Altium Vault - TI") (part "CMP-0078143-2"))
    )
    (comp (ref "TP41")
      (value "TESTPOINT")
      (footprint "TP_VIA_060RND040")
      (description "TEST POINT.  No entry in BOM.")
      (libsource (lib "Altium Vault - TI") (part "CMP-0078143-2"))
    )
    (comp (ref "U6")
      (value "BQ771807DPJR")
      (footprint "DPJ0008A")
      (description "Family 2-5S Overvoltage Protector with Internal Delay Timer, DPJ0008A (WSON-8)")
      (fields
        (field (name "ALTERNATE PARTNUMBER") "BQ771807DPJT")
        (field (name "MANUFACTURER") "Texas Instruments")
        (field (name "PARTNUMBER") "BQ771807DPJR")
      )
      (libsource (lib "Altium Vault - TI") (part "BQ77180x"))
    )
    (comp (ref "U7")
      (value "BQ771807DPJR")
      (footprint "DPJ0008A")
      (description "Family 2-5S Overvoltage Protector with Internal Delay Timer, DPJ0008A (WSON-8)")
      (fields
        (field (name "ALTERNATE PARTNUMBER") "BQ771807DPJT")
        (field (name "MANUFACTURER") "Texas Instruments")
        (field (name "PARTNUMBER") "BQ771807DPJR")
      )
      (libsource (lib "Altium Vault - TI") (part "BQ77180x"))
    )
  )
  (nets
    (net (code "1") (name "/CPACK+") (class "Default")
      (node (ref "C24") (pin "2") (pinfunction "2_2") (pintype "passive"))
      (node (ref "C29") (pin "2") (pinfunction "2_2") (pintype "passive"))
      (node (ref "E5") (pin "1") (pinfunction "1_1") (pintype "passive"))
      (node (ref "J20") (pin "1") (pinfunction "1_1") (pintype "passive"))
      (node (ref "J20") (pin "2") (pinfunction "2_2") (pintype "passive"))
      (node (ref "Q2") (pin "2") (pinfunction "S_2") (pintype "passive"))
      (node (ref "Q3") (pin "5") (pinfunction "D_5") (pintype "passive"))
      (node (ref "Q3") (pin "6") (pinfunction "D_6") (pintype "passive"))
      (node (ref "Q3") (pin "7") (pinfunction "D_7") (pintype "passive"))
      (node (ref "Q3") (pin "8") (pinfunction "D_8") (pintype "passive"))
      (node (ref "Q3") (pin "9") (pinfunction "D_9") (pintype "passive"))
      (node (ref "R46") (pin "1") (pinfunction "1_1") (pintype "passive"))
      (node (ref "R80") (pin "1") (pinfunction "1_1") (pintype "passive"))
      (node (ref "TP25") (pin "1") (pintype "passive"))
    )
    (net (code "2") (name "/FBAT") (class "Default")
      (node (ref "C23") (pin "1") (pinfunction "1_1") (pintype "passive"))
      (node (ref "C32") (pin "2") (pinfunction "2_2") (pintype "passive"))
      (node (ref "D4") (pin "2") (pinfunction "A_2") (pintype "passive"))
      (node (ref "F1") (pin "3") (pinfunction "Fuse_3") (pintype "passive"))
      (node (ref "NT2") (pin "1") (pinfunction "1_1") (pintype "passive"))
      (node (ref "Q3") (pin "1") (pinfunction "S_1") (pintype "passive"))
      (node (ref "Q3") (pin "2") (pinfunction "S_2") (pintype "passive"))
      (node (ref "Q3") (pin "3") (pinfunction "S_3") (pintype "passive"))
      (node (ref "Q8") (pin "1") (pinfunction "S_1") (pintype "passive"))
      (node (ref "Q8") (pin "2") (pinfunction "S_2") (pintype "passive"))
      (node (ref "Q8") (pin "3") (pinfunction "S_3") (pintype "passive"))
      (node (ref "R44") (pin "1") (pinfunction "1_1") (pintype "passive"))
      (node (ref "R50") (pin "1") (pinfunction "1_1") (pintype "passive"))
      (node (ref "R56") (pin "1") (pinfunction "1_1") (pintype "passive"))
      (node (ref "R59") (pin "1") (pinfunction "1_1") (pintype "passive"))
      (node (ref "TP26") (pin "1") (pintype "passive"))
    )
    (net (code "3") (name "/PACK+") (class "Default")
      (node (ref "C33") (pin "1") (pinfunction "1_1") (pintype "passive"))
      (node (ref "C35") (pin "2") (pinfunction "2_2") (pintype "passive"))
      (node (ref "D5") (pin "2") (pinfunction "A_2") (pintype "passive"))
      (node (ref "D6") (pin "2") (pinfunction "A_2") (pintype "passive"))
      (node (ref "E6") (pin "1") (pinfunction "1_1") (pintype "passive"))
      (node (ref "J21") (pin "3") (pinfunction "3_3") (pintype "passive"))
      (node (ref "J21") (pin "4") (pinfunction "4_4") (pintype "passive"))
      (node (ref "Q10") (pin "2") (pinfunction "S_2") (pintype "passive"))
      (node (ref "Q7") (pin "1") (pinfunction "S_1") (pintype "passive"))
      (node (ref "Q7") (pin "2") (pinfunction "S_2") (pintype "passive"))
      (node (ref "Q7") (pin "3") (pinfunction "S_3") (pintype "passive"))
      (node (ref "Q9") (pin "1") (pinfunction "S_1") (pintype "passive"))
      (node (ref "Q9") (pin "2") (pinfunction "S_2") (pintype "passive"))
      (node (ref "Q9") (pin "3") (pinfunction "S_3") (pintype "passive"))
      (node (ref "R51") (pin "2") (pinfunction "2_2") (pintype "passive"))
      (node (ref "R60") (pin "1") (pinfunction "1_1") (pintype "passive"))
      (node (ref "R61") (pin "1") (pinfunction "1_1") (pintype "passive"))
      (node (ref "R82") (pin "1") (pinfunction "1_1") (pintype "passive"))
      (node (ref "R84") (pin "1") (pinfunction "1_1") (pintype "passive"))
      (node (ref "TP27") (pin "1") (pintype "passive"))
    )
    (net (code "4") (name "1P") (class "Default")
      (node (ref "R71") (pin "1") (pinfunction "1_1") (pintype "passive"))
    )
    (net (code "5") (name "2P") (class "Default")
      (node (ref "R69") (pin "1") (pinfunction "1_1") (pintype "passive"))
    )
    (net (code "6") (name "3P") (class "Default")
      (node (ref "R68") (pin "1") (pinfunction "1_1") (pintype "passive"))
    )
    (net (code "7") (name "4P") (class "Default")
      (node (ref "R64") (pin "1") (pinfunction "1_1") (pintype "passive"))
    )
    (net (code "8") (name "5P") (class "Default")
      (node (ref "C27") (pin "1") (pinfunction "1_1") (pintype "passive"))
      (node (ref "C34") (pin "1") (pinfunction "1_1") (pintype "passive"))
      (node (ref "R49") (pin "1") (pinfunction "1_1") (pintype "passive"))
      (node (ref "R57") (pin "1") (pinfunction "1_1") (pintype "passive"))
      (node (ref "R62") (pin "1") (pinfunction "1_1") (pintype "passive"))
      (node (ref "U6") (pin "7") (pinfunction "VSS_7") (pintype "power_in"))
      (node (ref "U6") (pin "9") (pinfunction "PAD_9") (pintype "passive"))
    )
    (net (code "9") (name "6P") (class "Default")
      (node (ref "R48") (pin "1") (pinfunction "1_1") (pintype "passive"))
    )
    (net (code "10") (name "7P") (class "Default")
      (node (ref "R47") (pin "1") (pinfunction "1_1") (pintype "passive"))
    )
    (net (code "11") (name "8P") (class "Default")
      (node (ref "R45") (pin "1") (pinfunction "1_1") (pintype "passive"))
    )
    (net (code "12") (name "9P") (class "Default")
      (node (ref "R43") (pin "1") (pinfunction "1_1") (pintype "passive"))
    )
    (net (code "13") (name "10P") (class "Default")
      (node (ref "D3") (pin "2") (pinfunction "A_2") (pintype "passive"))
      (node (ref "F1") (pin "1") (pinfunction "Fuse_1") (pintype "passive"))
      (node (ref "NT2") (pin "2") (pinfunction "2_2") (pintype "passive"))
      (node (ref "R41") (pin "1") (pinfunction "1_1") (pintype "passive"))
      (node (ref "R42") (pin "1") (pinfunction "1_1") (pintype "passive"))
    )
    (net (code "14") (name "CD") (class "Default")
      (node (ref "Q5") (pin "2") (pinfunction "S_2") (pintype "passive"))
      (node (ref "Q6") (pin "2") (pinfunction "S_2") (pintype "passive"))
      (node (ref "Q7") (pin "5") (pinfunction "D_5") (pintype "passive"))
      (node (ref "Q7") (pin "6") (pinfunction "D_6") (pintype "passive"))
      (node (ref "Q7") (pin "7") (pinfunction "D_7") (pintype "passive"))
      (node (ref "Q7") (pin "8") (pinfunction "D_8") (pintype "passive"))
      (node (ref "Q7") (pin "9") (pinfunction "D_9") (pintype "passive"))
      (node (ref "Q8") (pin "5") (pinfunction "D_5") (pintype "passive"))
      (node (ref "Q8") (pin "6") (pinfunction "D_6") (pintype "passive"))
      (node (ref "Q8") (pin "7") (pinfunction "D_7") (pintype "passive"))
      (node (ref "Q8") (pin "8") (pinfunction "D_8") (pintype "passive"))
      (node (ref "Q8") (pin "9") (pinfunction "D_9") (pintype "passive"))
      (node (ref "Q9") (pin "5") (pinfunction "D_5") (pintype "passive"))
      (node (ref "Q9") (pin "6") (pinfunction "D_6") (pintype "passive"))
      (node (ref "Q9") (pin "7") (pinfunction "D_7") (pintype "passive"))
      (node (ref "Q9") (pin "8") (pinfunction "D_8") (pintype "passive"))
      (node (ref "Q9") (pin "9") (pinfunction "D_9") (pintype "passive"))
      (node (ref "R52") (pin "1") (pinfunction "1_1") (pintype "passive"))
      (node (ref "R53") (pin "1") (pinfunction "1_1") (pintype "passive"))
      (node (ref "R56") (pin "2") (pinfunction "2_2") (pintype "passive"))
      (node (ref "TP28") (pin "1") (pintype "passive"))
    )
    (net (code "15") (name "CHG") (class "Default")
      (node (ref "R72") (pin "1") (pinfunction "1_1") (pintype "passive"))
      (node (ref "TP35") (pin "1") (pintype "passive"))
    )
    (net (code "16") (name "DSG") (class "Default")
      (node (ref "D10") (pin "1") (pinfunction "K_1") (pintype "passive"))
      (node (ref "D11") (pin "1") (pinfunction "K_1") (pintype "passive"))
      (node (ref "R78") (pin "1") (pinfunction "1_1") (pintype "passive"))
      (node (ref "TP41") (pin "1") (pintype "passive"))
    )
    (net (code "17") (name "FUSE") (class "Default")
      (node (ref "R70") (pin "2") (pinfunction "2_2") (pintype "passive"))
    )
    (net (code "18") (name "LD") (class "Default")
      (node (ref "D13") (pin "1") (pinfunction "K_1") (pintype "passive"))
      (node (ref "R83") (pin "2") (pinfunction "2_2") (pintype "passive"))
      (node (ref "TP40") (pin "1") (pintype "passive"))
    )
    (net (code "19") (name "Net-(C23-Pad2)") (class "Default")
      (node (ref "C23") (pin "2") (pinfunction "2_2") (pintype "passive"))
      (node (ref "C24") (pin "1") (pinfunction "1_1") (pintype "passive"))
    )
    (net (code "20") (name "Net-(C29-Pad1)") (class "Default")
      (node (ref "C29") (pin "1") (pinfunction "1_1") (pintype "passive"))
      (node (ref "C31") (pin "2") (pinfunction "2_2") (pintype "passive"))
    )
    (net (code "21") (name "Net-(C32-Pad1)") (class "Default")
      (node (ref "C32") (pin "1") (pinfunction "1_1") (pintype "passive"))
      (node (ref "C33") (pin "2") (pinfunction "2_2") (pintype "passive"))
    )
    (net (code "22") (name "Net-(C35-Pad1)") (class "Default")
      (node (ref "C35") (pin "1") (pinfunction "1_1") (pintype "passive"))
      (node (ref "C37") (pin "2") (pinfunction "2_2") (pintype "passive"))
    )
    (net (code "23") (name "Net-(D3-K)") (class "Default")
      (node (ref "D3") (pin "1") (pinfunction "K_1") (pintype "passive"))
      (node (ref "R55") (pin "2") (pinfunction "2_2") (pintype "passive"))
    )
    (net (code "24") (name "Net-(D4-K)") (class "Default")
      (node (ref "D4") (pin "1") (pinfunction "K_1") (pintype "passive"))
      (node (ref "Q3") (pin "4") (pinfunction "G_4") (pintype "passive"))
      (node (ref "Q8") (pin "4") (pinfunction "G_4") (pintype "passive"))
      (node (ref "R59") (pin "2") (pinfunction "2_2") (pintype "passive"))
      (node (ref "R72") (pin "2") (pinfunction "2_2") (pintype "passive"))
      (node (ref "TP30") (pin "1") (pintype "passive"))
    )
    (net (code "25") (name "Net-(D5-K)") (class "Default")
      (node (ref "D5") (pin "1") (pinfunction "K_1") (pintype "passive"))
      (node (ref "Q10") (pin "3") (pinfunction "D_3") (pintype "passive"))
      (node (ref "R60") (pin "2") (pinfunction "2_2") (pintype "passive"))
      (node (ref "R65") (pin "2") (pinfunction "2_2") (pintype "passive"))
      (node (ref "R66") (pin "2") (pinfunction "2_2") (pintype "passive"))
      (node (ref "R76") (pin "2") (pinfunction "2_2") (pintype "passive"))
      (node (ref "R77") (pin "2") (pinfunction "2_2") (pintype "passive"))
      (node (ref "TP33") (pin "1") (pintype "passive"))
    )
    (net (code "26") (name "Net-(D6-K)") (class "Default")
      (node (ref "D6") (pin "1") (pinfunction "K_1") (pintype "passive"))
      (node (ref "Q10") (pin "1") (pinfunction "G_1") (pintype "passive"))
      (node (ref "R61") (pin "2") (pinfunction "2_2") (pintype "passive"))
      (node (ref "R67") (pin "1") (pinfunction "1_1") (pintype "passive"))
    )
    (net (code "27") (name "Net-(D7-A)") (class "Default")
      (node (ref "D7") (pin "1") (pinfunction "A_1") (pintype "passive"))
      (node (ref "R63") (pin "2") (pinfunction "2_2") (pintype "passive"))
    )
    (net (code "28") (name "Net-(D7-K)") (class "Default")
      (node (ref "C43") (pin "2") (pinfunction "2_2") (pintype "passive"))
      (node (ref "D7") (pin "3") (pinfunction "K_3") (pintype "passive"))
      (node (ref "D9") (pin "1") (pinfunction "K_1") (pintype "passive"))
      (node (ref "Q11") (pin "1") (pinfunction "G_1") (pintype "passive"))
      (node (ref "R54") (pin "2") (pinfunction "2_2") (pintype "passive"))
      (node (ref "R70") (pin "1") (pinfunction "1_1") (pintype "passive"))
      (node (ref "R75") (pin "2") (pinfunction "2_2") (pintype "passive"))
      (node (ref "TP34") (pin "1") (pintype "passive"))
    )
    (net (code "29") (name "Net-(D8-K)") (class "Default")
      (node (ref "D8") (pin "1") (pinfunction "K_1") (pintype "passive"))
      (node (ref "R67") (pin "2") (pinfunction "2_2") (pintype "passive"))
    )
    (net (code "30") (name "Net-(D10-A)") (class "Default")
      (node (ref "D10") (pin "2") (pinfunction "A_2") (pintype "passive"))
      (node (ref "R77") (pin "1") (pinfunction "1_1") (pintype "passive"))
    )
    (net (code "31") (name "Net-(F1-Heater)") (class "Default")
      (node (ref "F1") (pin "2") (pinfunction "Heater_2") (pintype "passive"))
      (node (ref "Q11") (pin "3") (pinfunction "D_3") (pintype "passive"))
      (node (ref "R58") (pin "1") (pinfunction "1_1") (pintype "passive"))
      (node (ref "TP29") (pin "1") (pintype "passive"))
    )
    (net (code "32") (name "Net-(Q2-D)") (class "Default")
      (node (ref "Q2") (pin "3") (pinfunction "D_3") (pintype "passive"))
      (node (ref "R44") (pin "2") (pinfunction "2_2") (pintype "passive"))
    )
    (net (code "33") (name "Net-(Q2-G)") (class "Default")
      (node (ref "Q2") (pin "1") (pinfunction "G_1") (pintype "passive"))
      (node (ref "Q5") (pin "1") (pinfunction "G_1") (pintype "passive"))
      (node (ref "R46") (pin "2") (pinfunction "2_2") (pintype "passive"))
      (node (ref "R53") (pin "2") (pinfunction "2_2") (pintype "passive"))
      (node (ref "R73") (pin "2") (pinfunction "2_2") (pintype "passive"))
      (node (ref "TP31") (pin "1") (pintype "passive"))
    )
    (net (code "34") (name "Net-(Q4-B)") (class "Default")
      (node (ref "Q4") (pin "1") (pinfunction "B_1") (pintype "passive"))
      (node (ref "R49") (pin "2") (pinfunction "2_2") (pintype "passive"))
    )
    (net (code "35") (name "Net-(Q4-C)") (class "Default")
      (node (ref "Q4") (pin "3") (pinfunction "C_3") (pintype "passive"))
      (node (ref "R54") (pin "1") (pinfunction "1_1") (pintype "passive"))
    )
    (net (code "36") (name "Net-(Q4-E)") (class "Default")
      (node (ref "Q4") (pin "2") (pinfunction "E_2") (pintype "passive"))
      (node (ref "U6") (pin "8") (pinfunction "OUT_8") (pintype "output"))
    )
    (net (code "37") (name "Net-(Q5-D)") (class "Default")
      (node (ref "Q5") (pin "3") (pinfunction "D_3") (pintype "passive"))
      (node (ref "R50") (pin "2") (pinfunction "2_2") (pintype "passive"))
    )
    (net (code "38") (name "Net-(Q6-D)") (class "Default")
      (node (ref "Q6") (pin "3") (pinfunction "D_3") (pintype "passive"))
      (node (ref "R51") (pin "1") (pinfunction "1_1") (pintype "passive"))
    )
    (net (code "39") (name "Net-(Q6-G)") (class "Default")
      (node (ref "Q6") (pin "1") (pinfunction "G_1") (pintype "passive"))
      (node (ref "R52") (pin "2") (pinfunction "2_2") (pintype "passive"))
      (node (ref "R74") (pin "2") (pinfunction "2_2") (pintype "passive"))
      (node (ref "TP32") (pin "1") (pintype "passive"))
    )
    (net (code "40") (name "Net-(Q7-G)") (class "Default")
      (node (ref "Q7") (pin "4") (pinfunction "G_4") (pintype "passive"))
      (node (ref "R65") (pin "1") (pinfunction "1_1") (pintype "passive"))
    )
    (net (code "41") (name "Net-(Q9-G)") (class "Default")
      (node (ref "Q9") (pin "4") (pinfunction "G_4") (pintype "passive"))
      (node (ref "R66") (pin "1") (pinfunction "1_1") (pintype "passive"))
    )
    (net (code "42") (name "Net-(R55-Pad1)") (class "Default")
      (node (ref "R55") (pin "1") (pinfunction "1_1") (pintype "passive"))
      (node (ref "R58") (pin "2") (pinfunction "2_2") (pintype "passive"))
    )
    (net (code "43") (name "Net-(R76-Pad1)") (class "Default")
      (node (ref "R76") (pin "1") (pinfunction "1_1") (pintype "passive"))
      (node (ref "R78") (pin "2") (pinfunction "2_2") (pintype "passive"))
    )
    (net (code "44") (name "Net-(R79-Pad1)") (class "Default")
      (node (ref "R79") (pin "1") (pinfunction "1_1") (pintype "passive"))
      (node (ref "R80") (pin "2") (pinfunction "2_2") (pintype "passive"))
    )
    (net (code "45") (name "Net-(R81-Pad1)") (class "Default")
      (node (ref "R81") (pin "1") (pinfunction "1_1") (pintype "passive"))
      (node (ref "R82") (pin "2") (pinfunction "2_2") (pintype "passive"))
    )
    (net (code "46") (name "Net-(R83-Pad1)") (class "Default")
      (node (ref "R83") (pin "1") (pinfunction "1_1") (pintype "passive"))
      (node (ref "R84") (pin "2") (pinfunction "2_2") (pintype "passive"))
    )
    (net (code "47") (name "Net-(U6-V1)") (class "Default")
      (node (ref "C30") (pin "1") (pinfunction "1_1") (pintype "passive"))
      (node (ref "C34") (pin "2") (pinfunction "2_2") (pintype "passive"))
      (node (ref "R48") (pin "2") (pinfunction "2_2") (pintype "passive"))
      (node (ref "U6") (pin "6") (pinfunction "V1_6") (pintype "input"))
    )
    (net (code "48") (name "Net-(U6-V2)") (class "Default")
      (node (ref "C28") (pin "1") (pinfunction "1_1") (pintype "passive"))
      (node (ref "C30") (pin "2") (pinfunction "2_2") (pintype "passive"))
      (node (ref "R47") (pin "2") (pinfunction "2_2") (pintype "passive"))
      (node (ref "U6") (pin "5") (pinfunction "V2_5") (pintype "input"))
    )
    (net (code "49") (name "Net-(U6-V3)") (class "Default")
      (node (ref "C26") (pin "1") (pinfunction "1_1") (pintype "passive"))
      (node (ref "C28") (pin "2") (pinfunction "2_2") (pintype "passive"))
      (node (ref "R45") (pin "2") (pinfunction "2_2") (pintype "passive"))
      (node (ref "U6") (pin "4") (pinfunction "V3_4") (pintype "input"))
    )
    (net (code "50") (name "Net-(U6-V4)") (class "Default")
      (node (ref "C25") (pin "1") (pinfunction "1_1") (pintype "passive"))
      (node (ref "C26") (pin "2") (pinfunction "2_2") (pintype "passive"))
      (node (ref "R43") (pin "2") (pinfunction "2_2") (pintype "passive"))
      (node (ref "U6") (pin "3") (pinfunction "V4_3") (pintype "input"))
    )
    (net (code "51") (name "Net-(U6-V5)") (class "Default")
      (node (ref "C25") (pin "2") (pinfunction "2_2") (pintype "passive"))
      (node (ref "R42") (pin "2") (pinfunction "2_2") (pintype "passive"))
      (node (ref "U6") (pin "2") (pinfunction "V5_2") (pintype "input"))
    )
    (net (code "52") (name "Net-(U6-VDD)") (class "Default")
      (node (ref "C27") (pin "2") (pinfunction "2_2") (pintype "passive"))
      (node (ref "R41") (pin "2") (pinfunction "2_2") (pintype "passive"))
      (node (ref "U6") (pin "1") (pinfunction "VDD_1") (pintype "power_in"))
    )
    (net (code "53") (name "Net-(U7-OUT)") (class "Default")
      (node (ref "R63") (pin "1") (pinfunction "1_1") (pintype "passive"))
      (node (ref "U7") (pin "8") (pinfunction "OUT_8") (pintype "output"))
    )
    (net (code "54") (name "Net-(U7-V1)") (class "Default")
      (node (ref "C41") (pin "1") (pinfunction "1_1") (pintype "passive"))
      (node (ref "C42") (pin "2") (pinfunction "2_2") (pintype "passive"))
      (node (ref "R71") (pin "2") (pinfunction "2_2") (pintype "passive"))
      (node (ref "U7") (pin "6") (pinfunction "V1_6") (pintype "input"))
    )
    (net (code "55") (name "Net-(U7-V2)") (class "Default")
      (node (ref "C40") (pin "1") (pinfunction "1_1") (pintype "passive"))
      (node (ref "C41") (pin "2") (pinfunction "2_2") (pintype "passive"))
      (node (ref "R69") (pin "2") (pinfunction "2_2") (pintype "passive"))
      (node (ref "U7") (pin "5") (pinfunction "V2_5") (pintype "input"))
    )
    (net (code "56") (name "Net-(U7-V3)") (class "Default")
      (node (ref "C38") (pin "1") (pinfunction "1_1") (pintype "passive"))
      (node (ref "C40") (pin "2") (pinfunction "2_2") (pintype "passive"))
      (node (ref "R68") (pin "2") (pinfunction "2_2") (pintype "passive"))
      (node (ref "U7") (pin "4") (pinfunction "V3_4") (pintype "input"))
    )
    (net (code "57") (name "Net-(U7-V4)") (class "Default")
      (node (ref "C36") (pin "1") (pinfunction "1_1") (pintype "passive"))
      (node (ref "C38") (pin "2") (pinfunction "2_2") (pintype "passive"))
      (node (ref "R64") (pin "2") (pinfunction "2_2") (pintype "passive"))
      (node (ref "U7") (pin "3") (pinfunction "V4_3") (pintype "input"))
    )
    (net (code "58") (name "Net-(U7-V5)") (class "Default")
      (node (ref "C36") (pin "2") (pinfunction "2_2") (pintype "passive"))
      (node (ref "R62") (pin "2") (pinfunction "2_2") (pintype "passive"))
      (node (ref "U7") (pin "2") (pinfunction "V5_2") (pintype "input"))
    )
    (net (code "59") (name "Net-(U7-VDD)") (class "Default")
      (node (ref "C39") (pin "2") (pinfunction "2_2") (pintype "passive"))
      (node (ref "R57") (pin "2") (pinfunction "2_2") (pintype "passive"))
      (node (ref "U7") (pin "1") (pinfunction "VDD_1") (pintype "power_in"))
    )
    (net (code "60") (name "PACK") (class "Default")
      (node (ref "D12") (pin "1") (pinfunction "K_1") (pintype "passive"))
      (node (ref "R79") (pin "2") (pinfunction "2_2") (pintype "passive"))
      (node (ref "R81") (pin "2") (pinfunction "2_2") (pintype "passive"))
      (node (ref "TP39") (pin "1") (pintype "passive"))
    )
    (net (code "61") (name "PCHG") (class "Default")
      (node (ref "R73") (pin "1") (pinfunction "1_1") (pintype "passive"))
      (node (ref "TP36") (pin "1") (pintype "passive"))
    )
    (net (code "62") (name "PDSG") (class "Default")
      (node (ref "R74") (pin "1") (pinfunction "1_1") (pintype "passive"))
      (node (ref "TP37") (pin "1") (pintype "passive"))
    )
    (net (code "63") (name "PGND") (class "Default")
      (node (ref "C31") (pin "1") (pinfunction "1_1") (pintype "passive"))
      (node (ref "C37") (pin "1") (pinfunction "1_1") (pintype "passive"))
      (node (ref "D8") (pin "2") (pinfunction "A_2") (pintype "passive"))
      (node (ref "E5") (pin "2") (pinfunction "2_2") (pintype "passive"))
      (node (ref "E6") (pin "2") (pinfunction "2_2") (pintype "passive"))
      (node (ref "J21") (pin "1") (pinfunction "1_1") (pintype "passive"))
      (node (ref "J21") (pin "2") (pinfunction "2_2") (pintype "passive"))
      (node (ref "TP38") (pin "1") (pintype "passive"))
    )
    (net (code "64") (name "VSS") (class "Default")
      (node (ref "C39") (pin "1") (pinfunction "1_1") (pintype "passive"))
      (node (ref "C42") (pin "1") (pinfunction "1_1") (pintype "passive"))
      (node (ref "C43") (pin "1") (pinfunction "1_1") (pintype "passive"))
      (node (ref "D11") (pin "2") (pinfunction "A_2") (pintype "passive"))
      (node (ref "D12") (pin "2") (pinfunction "A_2") (pintype "passive"))
      (node (ref "D13") (pin "2") (pinfunction "A_2") (pintype "passive"))
      (node (ref "D9") (pin "2") (pinfunction "A_2") (pintype "passive"))
      (node (ref "Q11") (pin "2") (pinfunction "S_2") (pintype "passive"))
      (node (ref "R75") (pin "1") (pinfunction "1_1") (pintype "passive"))
      (node (ref "U7") (pin "7") (pinfunction "VSS_7") (pintype "power_in"))
      (node (ref "U7") (pin "9") (pinfunction "PAD_9") (pintype "passive"))
    )
  )
)
